# USB_hub2.net
KiCad netlist of a schematic drawn in Altium Designer
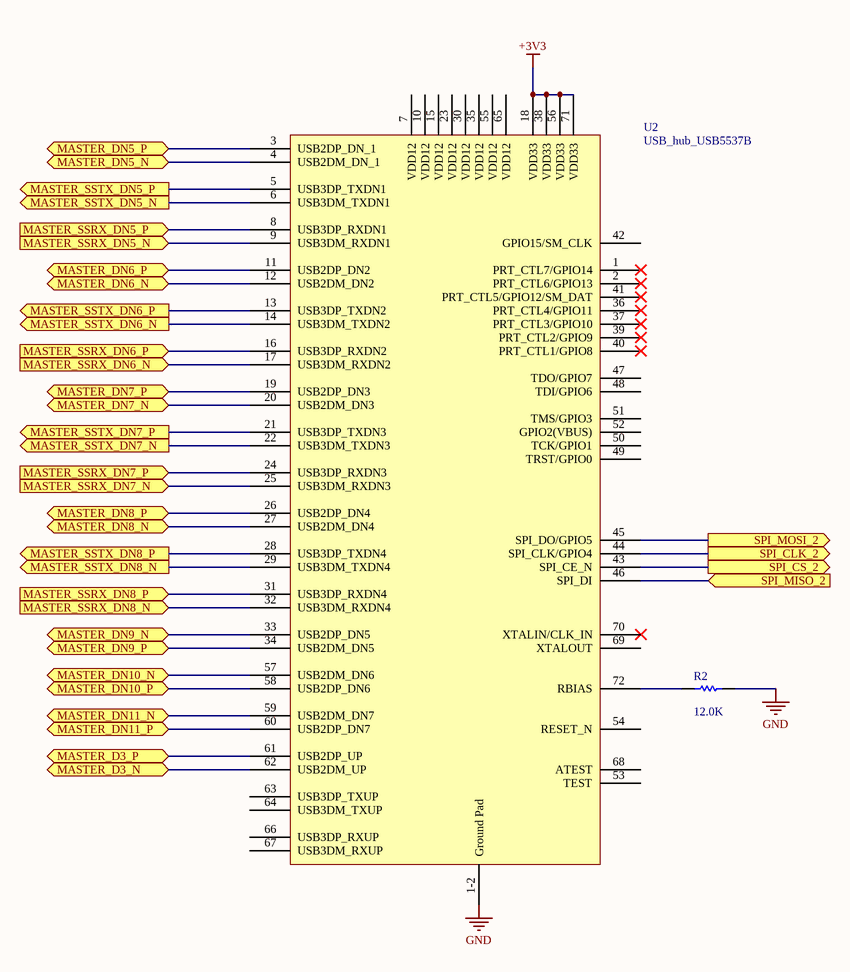
[diagram p0: USB_hub2.SchDoc]

(export (version "E")
  (design (tool "Eeschema 10.0.6"))
  (components
    (comp (ref "R2")
      (value "12.0K")
      (footprint "Miscellaneous Devices:RESC6332")
      (description "Resistor")
      (fields (field (name "Comment") "Res1") (field (name "PUBLISHER") "Altium Limited"))
      (libsource (lib "RSX_Resistors") (part "Res1"))
    )
    (comp (ref "U2")
      (value "USB_hub_USB5537B")
      (footprint "QFN50P1000X1000X100_HS-73N")
      (description "https://media.digikey.com/pdf/Data%20Sheets/Microchip%20PDFs/USB5537B.pdf")
      (libsource (lib "Backplane_Board") (part "USB_hub_USB5537B"))
    )
  )
  (nets
    (net (code "1") (name "+3V3") (class "Default")
      (node (ref "U2") (pin "18") (pinfunction "VDD33_18") (pintype "passive"))
      (node (ref "U2") (pin "38") (pinfunction "VDD33_38") (pintype "passive"))
      (node (ref "U2") (pin "56") (pinfunction "VDD33_56") (pintype "passive"))
      (node (ref "U2") (pin "71") (pinfunction "VDD33_71") (pintype "passive"))
    )
    (net (code "2") (name "/MASTER_D3_N") (class "Default")
      (node (ref "U2") (pin "62") (pinfunction "USB2DM_UP_62") (pintype "passive"))
    )
    (net (code "3") (name "/MASTER_D3_P") (class "Default")
      (node (ref "U2") (pin "61") (pinfunction "USB2DP_UP_61") (pintype "passive"))
    )
    (net (code "4") (name "/MASTER_DN5_N") (class "Default")
      (node (ref "U2") (pin "4") (pinfunction "USB2DM_DN_1_4") (pintype "passive"))
    )
    (net (code "5") (name "/MASTER_DN5_P") (class "Default")
      (node (ref "U2") (pin "3") (pinfunction "USB2DP_DN_1_3") (pintype "passive"))
    )
    (net (code "6") (name "/MASTER_DN6_N") (class "Default")
      (node (ref "U2") (pin "12") (pinfunction "USB2DM_DN2_12") (pintype "passive"))
    )
    (net (code "7") (name "/MASTER_DN6_P") (class "Default")
      (node (ref "U2") (pin "11") (pinfunction "USB2DP_DN2_11") (pintype "passive"))
    )
    (net (code "8") (name "/MASTER_DN7_N") (class "Default")
      (node (ref "U2") (pin "20") (pinfunction "USB2DM_DN3_20") (pintype "passive"))
    )
    (net (code "9") (name "/MASTER_DN7_P") (class "Default")
      (node (ref "U2") (pin "19") (pinfunction "USB2DP_DN3_19") (pintype "passive"))
    )
    (net (code "10") (name "/MASTER_DN8_N") (class "Default")
      (node (ref "U2") (pin "27") (pinfunction "USB2DM_DN4_27") (pintype "passive"))
    )
    (net (code "11") (name "/MASTER_DN8_P") (class "Default")
      (node (ref "U2") (pin "26") (pinfunction "USB2DP_DN4_26") (pintype "passive"))
    )
    (net (code "12") (name "/MASTER_DN9_N") (class "Default")
      (node (ref "U2") (pin "33") (pinfunction "USB2DP_DN5_33") (pintype "passive"))
    )
    (net (code "13") (name "/MASTER_DN9_P") (class "Default")
      (node (ref "U2") (pin "34") (pinfunction "USB2DM_DN5_34") (pintype "passive"))
    )
    (net (code "14") (name "/MASTER_DN10_N") (class "Default")
      (node (ref "U2") (pin "57") (pinfunction "USB2DM_DN6_57") (pintype "passive"))
    )
    (net (code "15") (name "/MASTER_DN10_P") (class "Default")
      (node (ref "U2") (pin "58") (pinfunction "USB2DP_DN6_58") (pintype "passive"))
    )
    (net (code "16") (name "/MASTER_DN11_N") (class "Default")
      (node (ref "U2") (pin "59") (pinfunction "USB2DM_DN7_59") (pintype "passive"))
    )
    (net (code "17") (name "/MASTER_DN11_P") (class "Default")
      (node (ref "U2") (pin "60") (pinfunction "USB2DP_DN7_60") (pintype "passive"))
    )
    (net (code "18") (name "/MASTER_SSRX_DN5_N") (class "Default")
      (node (ref "U2") (pin "9") (pinfunction "USB3DM_RXDN1_9") (pintype "passive"))
    )
    (net (code "19") (name "/MASTER_SSRX_DN5_P") (class "Default")
      (node (ref "U2") (pin "8") (pinfunction "USB3DP_RXDN1_8") (pintype "passive"))
    )
    (net (code "20") (name "/MASTER_SSRX_DN6_N") (class "Default")
      (node (ref "U2") (pin "17") (pinfunction "USB3DM_RXDN2_17") (pintype "passive"))
    )
    (net (code "21") (name "/MASTER_SSRX_DN6_P") (class "Default")
      (node (ref "U2") (pin "16") (pinfunction "USB3DP_RXDN2_16") (pintype "passive"))
    )
    (net (code "22") (name "/MASTER_SSRX_DN7_N") (class "Default")
      (node (ref "U2") (pin "25") (pinfunction "USB3DM_RXDN3_25") (pintype "passive"))
    )
    (net (code "23") (name "/MASTER_SSRX_DN7_P") (class "Default")
      (node (ref "U2") (pin "24") (pinfunction "USB3DP_RXDN3_24") (pintype "passive"))
    )
    (net (code "24") (name "/MASTER_SSRX_DN8_N") (class "Default")
      (node (ref "U2") (pin "32") (pinfunction "USB3DM_RXDN4_32") (pintype "passive"))
    )
    (net (code "25") (name "/MASTER_SSRX_DN8_P") (class "Default")
      (node (ref "U2") (pin "31") (pinfunction "USB3DP_RXDN4_31") (pintype "passive"))
    )
    (net (code "26") (name "/MASTER_SSTX_DN5_N") (class "Default")
      (node (ref "U2") (pin "6") (pinfunction "USB3DM_TXDN1_6") (pintype "passive"))
    )
    (net (code "27") (name "/MASTER_SSTX_DN5_P") (class "Default")
      (node (ref "U2") (pin "5") (pinfunction "USB3DP_TXDN1_5") (pintype "passive"))
    )
    (net (code "28") (name "/MASTER_SSTX_DN6_N") (class "Default")
      (node (ref "U2") (pin "14") (pinfunction "USB3DM_TXDN2_14") (pintype "passive"))
    )
    (net (code "29") (name "/MASTER_SSTX_DN6_P") (class "Default")
      (node (ref "U2") (pin "13") (pinfunction "USB3DP_TXDN2_13") (pintype "passive"))
    )
    (net (code "30") (name "/MASTER_SSTX_DN7_N") (class "Default")
      (node (ref "U2") (pin "22") (pinfunction "USB3DM_TXDN3_22") (pintype "passive"))
    )
    (net (code "31") (name "/MASTER_SSTX_DN7_P") (class "Default")
      (node (ref "U2") (pin "21") (pinfunction "USB3DP_TXDN3_21") (pintype "passive"))
    )
    (net (code "32") (name "/MASTER_SSTX_DN8_N") (class "Default")
      (node (ref "U2") (pin "29") (pinfunction "USB3DM_TXDN4_29") (pintype "passive"))
    )
    (net (code "33") (name "/MASTER_SSTX_DN8_P") (class "Default")
      (node (ref "U2") (pin "28") (pinfunction "USB3DP_TXDN4_28") (pintype "passive"))
    )
    (net (code "34") (name "/SPI_CLK_2") (class "Default")
      (node (ref "U2") (pin "44") (pinfunction "SPI_CLK/GPIO4_44") (pintype "passive"))
    )
    (net (code "35") (name "/SPI_CS_2") (class "Default")
      (node (ref "U2") (pin "43") (pinfunction "SPI_CE_N_43") (pintype "passive"))
    )
    (net (code "36") (name "/SPI_MISO_2") (class "Default")
      (node (ref "U2") (pin "46") (pinfunction "SPI_DI_46") (pintype "passive"))
    )
    (net (code "37") (name "/SPI_MOSI_2") (class "Default")
      (node (ref "U2") (pin "45") (pinfunction "SPI_DO/GPIO5_45") (pintype "passive"))
    )
    (net (code "38") (name "GND") (class "Default")
      (node (ref "R2") (pin "2") (pinfunction "2_2") (pintype "passive"))
      (node (ref "U2") (pin "1-2") (pinfunction "Ground_Pad_1-2") (pintype "passive"))
    )
    (net (code "39") (name "Net-(U2-RBIAS)") (class "Default")
      (node (ref "R2") (pin "1") (pinfunction "1_1") (pintype "passive"))
      (node (ref "U2") (pin "72") (pinfunction "RBIAS_72") (pintype "passive"))
    )
    (net (code "40") (name "unconnected-(U2-ATEST-Pad68)") (class "Default")
      (node (ref "U2") (pin "68") (pinfunction "ATEST_68") (pintype "passive"))
    )
    (net (code "41") (name "unconnected-(U2-GPIO2(VBUS)-Pad52)") (class "Default")
      (node (ref "U2") (pin "52") (pinfunction "GPIO2(VBUS)_52") (pintype "passive"))
    )
    (net (code "42") (name "unconnected-(U2-GPIO15{slash}SM_CLK-Pad42)") (class "Default")
      (node (ref "U2") (pin "42") (pinfunction "GPIO15/SM_CLK_42") (pintype "passive"))
    )
    (net (code "43") (name "unconnected-(U2-PRT_CTL1{slash}GPIO8-Pad40)") (class "Default")
      (node (ref "U2") (pin "40") (pinfunction "PRT_CTL1/GPIO8_40") (pintype "passive+no_connect"))
    )
    (net (code "44") (name "unconnected-(U2-PRT_CTL2{slash}GPIO9-Pad39)") (class "Default")
      (node (ref "U2") (pin "39") (pinfunction "PRT_CTL2/GPIO9_39") (pintype "passive+no_connect"))
    )
    (net (code "45") (name "unconnected-(U2-PRT_CTL3{slash}GPIO10-Pad37)") (class "Default")
      (node (ref "U2") (pin "37") (pinfunction "PRT_CTL3/GPIO10_37") (pintype "passive+no_connect"))
    )
    (net (code "46") (name "unconnected-(U2-PRT_CTL4{slash}GPIO11-Pad36)") (class "Default")
      (node (ref "U2") (pin "36") (pinfunction "PRT_CTL4/GPIO11_36") (pintype "passive+no_connect"))
    )
    (net (code "47") (name "unconnected-(U2-PRT_CTL5{slash}GPIO12{slash}SM_DAT-Pad41)") (class "Default")
      (node (ref "U2") (pin "41") (pinfunction "PRT_CTL5/GPIO12/SM_DAT_41") (pintype "passive+no_connect"))
    )
    (net (code "48") (name "unconnected-(U2-PRT_CTL6{slash}GPIO13-Pad2)") (class "Default")
      (node (ref "U2") (pin "2") (pinfunction "PRT_CTL6/GPIO13_2") (pintype "passive+no_connect"))
    )
    (net (code "49") (name "unconnected-(U2-PRT_CTL7{slash}GPIO14-Pad1)") (class "Default")
      (node (ref "U2") (pin "1") (pinfunction "PRT_CTL7/GPIO14_1") (pintype "passive+no_connect"))
    )
    (net (code "50") (name "unconnected-(U2-RESET_N-Pad54)") (class "Default")
      (node (ref "U2") (pin "54") (pinfunction "RESET_N_54") (pintype "passive"))
    )
    (net (code "51") (name "unconnected-(U2-TCK{slash}GPIO1-Pad50)") (class "Default")
      (node (ref "U2") (pin "50") (pinfunction "TCK/GPIO1_50") (pintype "passive"))
    )
    (net (code "52") (name "unconnected-(U2-TDI{slash}GPIO6-Pad48)") (class "Default")
      (node (ref "U2") (pin "48") (pinfunction "TDI/GPIO6_48") (pintype "passive"))
    )
    (net (code "53") (name "unconnected-(U2-TDO{slash}GPIO7-Pad47)") (class "Default")
      (node (ref "U2") (pin "47") (pinfunction "TDO/GPIO7_47") (pintype "passive"))
    )
    (net (code "54") (name "unconnected-(U2-TEST-Pad53)") (class "Default")
      (node (ref "U2") (pin "53") (pinfunction "TEST_53") (pintype "passive"))
    )
    (net (code "55") (name "unconnected-(U2-TMS{slash}GPIO3-Pad51)") (class "Default")
      (node (ref "U2") (pin "51") (pinfunction "TMS/GPIO3_51") (pintype "passive"))
    )
    (net (code "56") (name "unconnected-(U2-TRST{slash}GPIO0-Pad49)") (class "Default")
      (node (ref "U2") (pin "49") (pinfunction "TRST/GPIO0_49") (pintype "passive"))
    )
    (net (code "57") (name "unconnected-(U2-USB3DM_RXUP-Pad67)") (class "Default")
      (node (ref "U2") (pin "67") (pinfunction "USB3DM_RXUP_67") (pintype "passive"))
    )
    (net (code "58") (name "unconnected-(U2-USB3DM_TXUP-Pad64)") (class "Default")
      (node (ref "U2") (pin "64") (pinfunction "USB3DM_TXUP_64") (pintype "passive"))
    )
    (net (code "59") (name "unconnected-(U2-USB3DP_RXUP-Pad66)") (class "Default")
      (node (ref "U2") (pin "66") (pinfunction "USB3DP_RXUP_66") (pintype "passive"))
    )
    (net (code "60") (name "unconnected-(U2-USB3DP_TXUP-Pad63)") (class "Default")
      (node (ref "U2") (pin "63") (pinfunction "USB3DP_TXUP_63") (pintype "passive"))
    )
    (net (code "61") (name "unconnected-(U2-VDD12-Pad7)") (class "Default")
      (node (ref "U2") (pin "7") (pinfunction "VDD12_7") (pintype "passive"))
    )
    (net (code "62") (name "unconnected-(U2-VDD12-Pad10)") (class "Default")
      (node (ref "U2") (pin "10") (pinfunction "VDD12_10") (pintype "passive"))
    )
    (net (code "63") (name "unconnected-(U2-VDD12-Pad15)") (class "Default")
      (node (ref "U2") (pin "15") (pinfunction "VDD12_15") (pintype "passive"))
    )
    (net (code "64") (name "unconnected-(U2-VDD12-Pad23)") (class "Default")
      (node (ref "U2") (pin "23") (pinfunction "VDD12_23") (pintype "passive"))
    )
    (net (code "65") (name "unconnected-(U2-VDD12-Pad30)") (class "Default")
      (node (ref "U2") (pin "30") (pinfunction "VDD12_30") (pintype "passive"))
    )
    (net (code "66") (name "unconnected-(U2-VDD12-Pad35)") (class "Default")
      (node (ref "U2") (pin "35") (pinfunction "VDD12_35") (pintype "passive"))
    )
    (net (code "67") (name "unconnected-(U2-VDD12-Pad55)") (class "Default")
      (node (ref "U2") (pin "55") (pinfunction "VDD12_55") (pintype "passive"))
    )
    (net (code "68") (name "unconnected-(U2-VDD12-Pad65)") (class "Default")
      (node (ref "U2") (pin "65") (pinfunction "VDD12_65") (pintype "passive"))
    )
    (net (code "69") (name "unconnected-(U2-XTALIN{slash}CLK_IN-Pad70)") (class "Default")
      (node (ref "U2") (pin "70") (pinfunction "XTALIN/CLK_IN_70") (pintype "passive+no_connect"))
    )
    (net (code "70") (name "unconnected-(U2-XTALOUT-Pad69)") (class "Default")
      (node (ref "U2") (pin "69") (pinfunction "XTALOUT_69") (pintype "passive"))
    )
  )
)
